# Sheet.net
KiCad netlist of a schematic drawn in Altium Designer
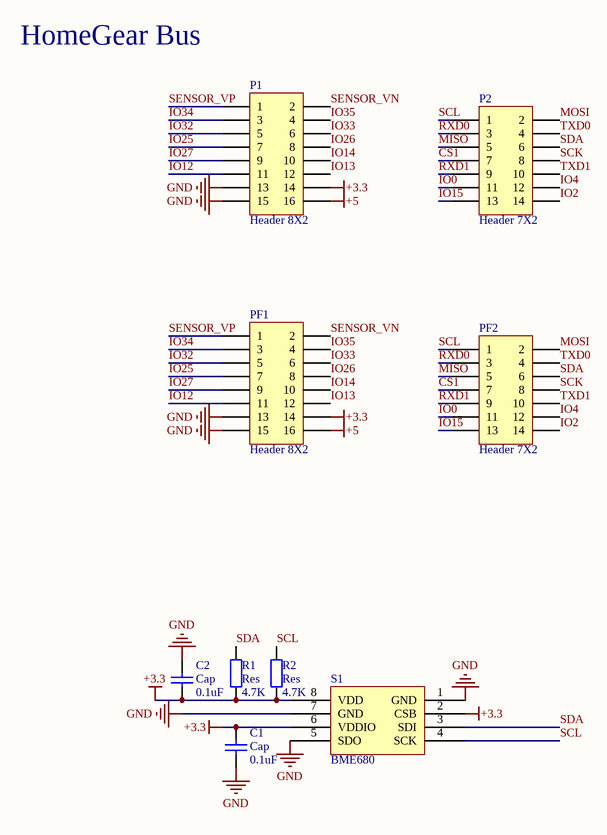
[diagram p0: Sheet.SchDoc]

(export (version "E")
  (design (tool "Eeschema 10.0.6"))
  (components
    (comp (ref "C1")
      (value "Cap")
      (footprint "MY0603")
      (description "Capacitor")
      (fields (field (name "ALTIUM_VALUE") "0.1uF") (field (name "PUBLISHER") "Altium Limited"))
      (libsource (lib "Miscellaneous Devices") (part "Cap"))
    )
    (comp (ref "C2")
      (value "Cap")
      (footprint "MY0603")
      (description "Capacitor")
      (fields (field (name "ALTIUM_VALUE") "0.1uF") (field (name "PUBLISHER") "Altium Limited"))
      (libsource (lib "Miscellaneous Devices") (part "Cap"))
    )
    (comp (ref "P1")
      (value "Header 8X2")
      (footprint "SMD_PIN_HDR8x2_2.0MM")
      (description "Header, 8-Pin, Dual row")
      (fields (field (name "PUBLISHER") "Altium Limited"))
      (libsource (lib "Miscellaneous Connectors") (part "Header 8X2"))
    )
    (comp (ref "P2")
      (value "Header 7X2")
      (footprint "SMD_PIN_HDR7x2_2.0MM")
      (description "Header, 7-Pin, Dual row")
      (fields (field (name "PUBLISHER") "Altium Limited"))
      (libsource (lib "Miscellaneous Connectors") (part "Header 7X2"))
    )
    (comp (ref "PF1")
      (value "Header 8X2")
      (footprint "SMD_FEM_HDR8x2_2.0MM")
      (description "Header, 8-Pin, Dual row")
      (fields (field (name "PUBLISHER") "Altium Limited"))
      (libsource (lib "Miscellaneous Connectors") (part "Header 8X2"))
    )
    (comp (ref "PF2")
      (value "Header 7X2")
      (footprint "SMD_FEM_HDR7x2_2.0MM")
      (description "Header, 7-Pin, Dual row")
      (fields (field (name "PUBLISHER") "Altium Limited"))
      (libsource (lib "Miscellaneous Connectors") (part "Header 7X2"))
    )
    (comp (ref "R1")
      (value "Res")
      (footprint "MY0603")
      (description "Resistor")
      (fields (field (name "ALTIUM_VALUE") "4.7K") (field (name "PUBLISHER") "Altium Limited"))
      (libsource (lib "Miscellaneous Devices") (part "Res2"))
    )
    (comp (ref "R2")
      (value "Res")
      (footprint "MY0603")
      (description "Resistor")
      (fields (field (name "ALTIUM_VALUE") "4.7K") (field (name "PUBLISHER") "Altium Limited"))
      (libsource (lib "Miscellaneous Devices") (part "Res2"))
    )
    (comp (ref "S1") (value "BME680") (footprint "LGA-8") (libsource (lib "我的元件库") (part "BME680")))
  )
  (nets
    (net (code "1") (name "+3.3") (class "Default")
      (node (ref "C1") (pin "2") (pinfunction "2_2") (pintype "passive"))
      (node (ref "C2") (pin "1") (pinfunction "1_1") (pintype "passive"))
      (node (ref "P1") (pin "14") (pinfunction "14_14") (pintype "passive"))
      (node (ref "PF1") (pin "14") (pinfunction "14_14") (pintype "passive"))
      (node (ref "R1") (pin "1") (pinfunction "1_1") (pintype "passive"))
      (node (ref "R2") (pin "1") (pinfunction "1_1") (pintype "passive"))
      (node (ref "S1") (pin "2") (pinfunction "CSB_2") (pintype "passive"))
      (node (ref "S1") (pin "6") (pinfunction "VDDIO_6") (pintype "passive"))
      (node (ref "S1") (pin "8") (pinfunction "VDD_8") (pintype "passive"))
    )
    (net (code "2") (name "+5") (class "Default")
      (node (ref "P1") (pin "16") (pinfunction "16_16") (pintype "passive"))
      (node (ref "PF1") (pin "16") (pinfunction "16_16") (pintype "passive"))
    )
    (net (code "3") (name "/CS1") (class "Default")
      (node (ref "P2") (pin "7") (pinfunction "7_7") (pintype "passive"))
      (node (ref "PF2") (pin "7") (pinfunction "7_7") (pintype "passive"))
    )
    (net (code "4") (name "/IO0") (class "Default")
      (node (ref "P2") (pin "11") (pinfunction "11_11") (pintype "passive"))
      (node (ref "PF2") (pin "11") (pinfunction "11_11") (pintype "passive"))
    )
    (net (code "5") (name "/IO2") (class "Default")
      (node (ref "P2") (pin "14") (pinfunction "14_14") (pintype "passive"))
      (node (ref "PF2") (pin "14") (pinfunction "14_14") (pintype "passive"))
    )
    (net (code "6") (name "/IO4") (class "Default")
      (node (ref "P2") (pin "12") (pinfunction "12_12") (pintype "passive"))
      (node (ref "PF2") (pin "12") (pinfunction "12_12") (pintype "passive"))
    )
    (net (code "7") (name "/IO12") (class "Default")
      (node (ref "P1") (pin "11") (pinfunction "11_11") (pintype "passive"))
      (node (ref "PF1") (pin "11") (pinfunction "11_11") (pintype "passive"))
    )
    (net (code "8") (name "/IO13") (class "Default")
      (node (ref "P1") (pin "12") (pinfunction "12_12") (pintype "passive"))
      (node (ref "PF1") (pin "12") (pinfunction "12_12") (pintype "passive"))
    )
    (net (code "9") (name "/IO14") (class "Default")
      (node (ref "P1") (pin "10") (pinfunction "10_10") (pintype "passive"))
      (node (ref "PF1") (pin "10") (pinfunction "10_10") (pintype "passive"))
    )
    (net (code "10") (name "/IO15") (class "Default")
      (node (ref "P2") (pin "13") (pinfunction "13_13") (pintype "passive"))
      (node (ref "PF2") (pin "13") (pinfunction "13_13") (pintype "passive"))
    )
    (net (code "11") (name "/IO25") (class "Default")
      (node (ref "P1") (pin "7") (pinfunction "7_7") (pintype "passive"))
      (node (ref "PF1") (pin "7") (pinfunction "7_7") (pintype "passive"))
    )
    (net (code "12") (name "/IO26") (class "Default")
      (node (ref "P1") (pin "8") (pinfunction "8_8") (pintype "passive"))
      (node (ref "PF1") (pin "8") (pinfunction "8_8") (pintype "passive"))
    )
    (net (code "13") (name "/IO27") (class "Default")
      (node (ref "P1") (pin "9") (pinfunction "9_9") (pintype "passive"))
      (node (ref "PF1") (pin "9") (pinfunction "9_9") (pintype "passive"))
    )
    (net (code "14") (name "/IO32") (class "Default")
      (node (ref "P1") (pin "5") (pinfunction "5_5") (pintype "passive"))
      (node (ref "PF1") (pin "5") (pinfunction "5_5") (pintype "passive"))
    )
    (net (code "15") (name "/IO33") (class "Default")
      (node (ref "P1") (pin "6") (pinfunction "6_6") (pintype "passive"))
      (node (ref "PF1") (pin "6") (pinfunction "6_6") (pintype "passive"))
    )
    (net (code "16") (name "/IO34") (class "Default")
      (node (ref "P1") (pin "3") (pinfunction "3_3") (pintype "passive"))
      (node (ref "PF1") (pin "3") (pinfunction "3_3") (pintype "passive"))
    )
    (net (code "17") (name "/IO35") (class "Default")
      (node (ref "P1") (pin "4") (pinfunction "4_4") (pintype "passive"))
      (node (ref "PF1") (pin "4") (pinfunction "4_4") (pintype "passive"))
    )
    (net (code "18") (name "/MISO") (class "Default")
      (node (ref "P2") (pin "5") (pinfunction "5_5") (pintype "passive"))
      (node (ref "PF2") (pin "5") (pinfunction "5_5") (pintype "passive"))
    )
    (net (code "19") (name "/MOSI") (class "Default")
      (node (ref "P2") (pin "2") (pinfunction "2_2") (pintype "passive"))
      (node (ref "PF2") (pin "2") (pinfunction "2_2") (pintype "passive"))
    )
    (net (code "20") (name "/RXD0") (class "Default")
      (node (ref "P2") (pin "3") (pinfunction "3_3") (pintype "passive"))
      (node (ref "PF2") (pin "3") (pinfunction "3_3") (pintype "passive"))
    )
    (net (code "21") (name "/RXD1") (class "Default")
      (node (ref "P2") (pin "9") (pinfunction "9_9") (pintype "passive"))
      (node (ref "PF2") (pin "9") (pinfunction "9_9") (pintype "passive"))
    )
    (net (code "22") (name "/SCK") (class "Default")
      (node (ref "P2") (pin "8") (pinfunction "8_8") (pintype "passive"))
      (node (ref "PF2") (pin "8") (pinfunction "8_8") (pintype "passive"))
    )
    (net (code "23") (name "/SCL") (class "Default")
      (node (ref "P2") (pin "1") (pinfunction "1_1") (pintype "passive"))
      (node (ref "PF2") (pin "1") (pinfunction "1_1") (pintype "passive"))
      (node (ref "R2") (pin "2") (pinfunction "2_2") (pintype "passive"))
      (node (ref "S1") (pin "4") (pinfunction "SCK_4") (pintype "passive"))
    )
    (net (code "24") (name "/SDA") (class "Default")
      (node (ref "P2") (pin "6") (pinfunction "6_6") (pintype "passive"))
      (node (ref "PF2") (pin "6") (pinfunction "6_6") (pintype "passive"))
      (node (ref "R1") (pin "2") (pinfunction "2_2") (pintype "passive"))
      (node (ref "S1") (pin "3") (pinfunction "SDI_3") (pintype "passive"))
    )
    (net (code "25") (name "/SENSOR_VN") (class "Default")
      (node (ref "P1") (pin "2") (pinfunction "2_2") (pintype "passive"))
      (node (ref "PF1") (pin "2") (pinfunction "2_2") (pintype "passive"))
    )
    (net (code "26") (name "/SENSOR_VP") (class "Default")
      (node (ref "P1") (pin "1") (pinfunction "1_1") (pintype "passive"))
      (node (ref "PF1") (pin "1") (pinfunction "1_1") (pintype "passive"))
    )
    (net (code "27") (name "/TXD0") (class "Default")
      (node (ref "P2") (pin "4") (pinfunction "4_4") (pintype "passive"))
      (node (ref "PF2") (pin "4") (pinfunction "4_4") (pintype "passive"))
    )
    (net (code "28") (name "/TXD1") (class "Default")
      (node (ref "P2") (pin "10") (pinfunction "10_10") (pintype "passive"))
      (node (ref "PF2") (pin "10") (pinfunction "10_10") (pintype "passive"))
    )
    (net (code "29") (name "GND") (class "Default")
      (node (ref "C1") (pin "1") (pinfunction "1_1") (pintype "passive"))
      (node (ref "C2") (pin "2") (pinfunction "2_2") (pintype "passive"))
      (node (ref "P1") (pin "13") (pinfunction "13_13") (pintype "passive"))
      (node (ref "P1") (pin "15") (pinfunction "15_15") (pintype "passive"))
      (node (ref "PF1") (pin "13") (pinfunction "13_13") (pintype "passive"))
      (node (ref "PF1") (pin "15") (pinfunction "15_15") (pintype "passive"))
      (node (ref "S1") (pin "1") (pinfunction "GND_1") (pintype "passive"))
      (node (ref "S1") (pin "5") (pinfunction "SDO_5") (pintype "passive"))
      (node (ref "S1") (pin "7") (pinfunction "GND_7") (pintype "passive"))
    )
  )
)
